# DarlingtonBJTArray.net
KiCad netlist of a schematic drawn in Altium Designer
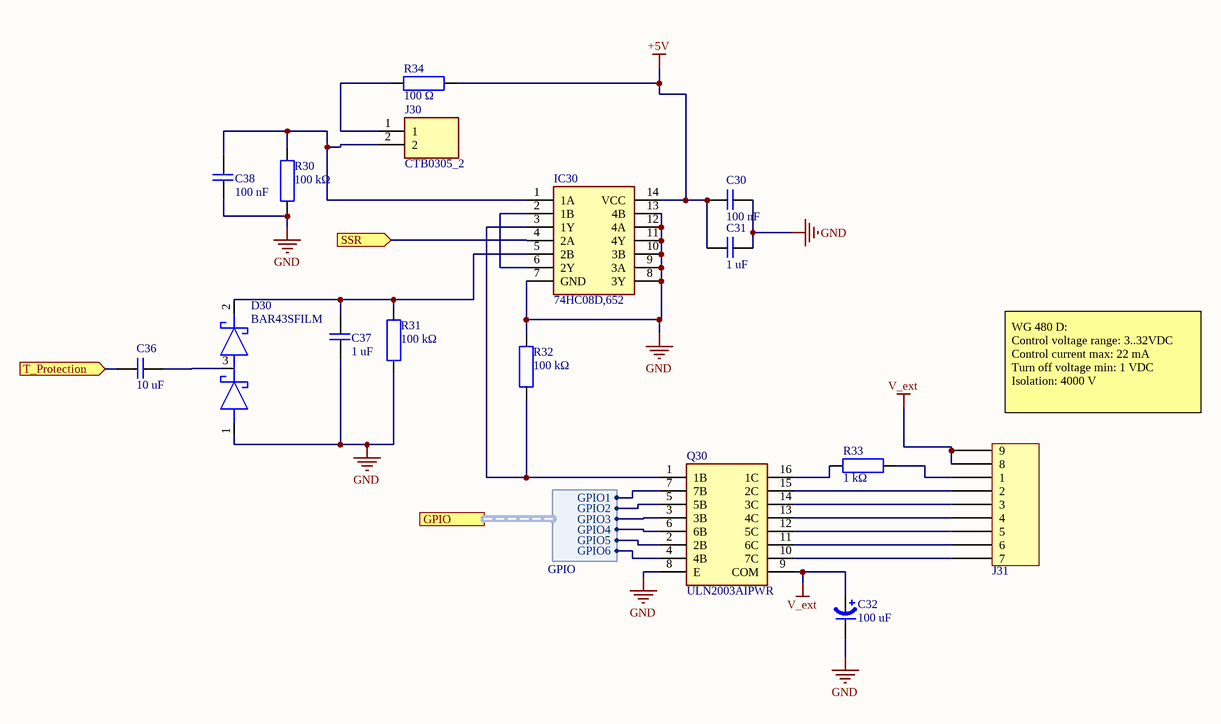
[diagram p0: DarlingtonBJTArray.SchDoc]

(export (version "E")
  (design (tool "Eeschema 10.0.6"))
  (components
    (comp (ref "C30")
      (value "100 nF")
      (footprint "1206 MLCC")
      (description "Generic MLCC")
      (libsource (lib "passives") (part "Capacitor"))
    )
    (comp (ref "C31")
      (value "1 uF")
      (footprint "1206 MLCC")
      (description "Generic MLCC")
      (libsource (lib "passives") (part "Capacitor"))
    )
    (comp (ref "C32")
      (value "100 uF")
      (footprint "RADIAL 8x11")
      (description "Electrolytic capacitor")
      (libsource (lib "passives") (part "Elco"))
    )
    (comp (ref "C36")
      (value "10 uF")
      (footprint "1210 MLCC")
      (description "Generic MLCC")
      (libsource (lib "passives") (part "Capacitor"))
    )
    (comp (ref "C37")
      (value "1 uF")
      (footprint "1206 MLCC")
      (description "Generic MLCC")
      (libsource (lib "passives") (part "Capacitor"))
    )
    (comp (ref "C38")
      (value "100 nF")
      (footprint "1206 MLCC")
      (description "Generic MLCC")
      (libsource (lib "passives") (part "Capacitor"))
    )
    (comp (ref "D30")
      (value "BAR43SFILM")
      (footprint "SamacSys:SOT105P242X150-3N")
      (description "Dual 0.1A small signl schottky")
      (fields (field (name "MOUSER PART NUMBER") "511-BAR43SFILM"))
      (libsource (lib "SamacSys") (part "BAR43SFILM"))
    )
    (comp (ref "IC30")
      (value "74HC08D,652")
      (footprint "SamacSys:SOIC127P600X175-14N")
      (description "Integrated Circuit")
      (fields (field (name "MOUSER PART NUMBER") "771-HC08D652"))
      (libsource (lib "*") (part "74HC08D,652"))
    )
    (comp (ref "J30")
      (value "CTB0305_2")
      (footprint "SamacSys:CTB03052")
      (description "Connector")
      (fields (field (name "MANUFACTURER_PART_NUMBER") "CTB0305/2"))
      (libsource (lib "*") (part "CTB0305_2"))
    )
    (comp (ref "J31")
      (value "9P terminal block")
      (footprint "9P terminal block 3.50mm")
      (description "3.50mm 9p terminal block")
      (libsource (lib "passives") (part "9P terminal block"))
    )
    (comp (ref "Q30")
      (value "ULN2003AIPWR")
      (footprint "SamacSys:SOP65P640X120-16N")
      (description "Transistor")
      (fields (field (name "MOUSER PART NUMBER") "595-ULN2003AIPWR"))
      (libsource (lib "*") (part "ULN2003AIPWR"))
    )
    (comp (ref "R30")
      (value "100 kΩ")
      (footprint "1206 RES")
      (description "Generic SMD resistor")
      (libsource (lib "") (part "Resitor_1"))
    )
    (comp (ref "R31")
      (value "100 kΩ")
      (footprint "1206 RES")
      (description "Generic SMD resistor")
      (libsource (lib "") (part "Resitor_1"))
    )
    (comp (ref "R32")
      (value "100 kΩ")
      (footprint "1206 RES")
      (description "Generic SMD resistor")
      (libsource (lib "") (part "Resitor_1"))
    )
    (comp (ref "R33")
      (value "1 kΩ")
      (footprint "1206 RES")
      (description "Generic SMD resistor")
      (libsource (lib "passives") (part "Resitor"))
    )
    (comp (ref "R34")
      (value "100 Ω")
      (footprint "1206 RES")
      (description "Generic SMD resistor")
      (libsource (lib "passives") (part "Resitor"))
    )
  )
  (nets
    (net (code "2") (name "+5V") (class "Default")
      (node (ref "C30") (pin "1") (pintype "passive"))
      (node (ref "C31") (pin "1") (pintype "passive"))
      (node (ref "IC30") (pin "14") (pinfunction "VCC_14") (pintype "passive"))
      (node (ref "R34") (pin "1") (pintype "passive"))
    )
    (net (code "3") (name "/GPIO1") (class "Default")
      (node (ref "Q30") (pin "7") (pinfunction "7B_7") (pintype "passive"))
    )
    (net (code "4") (name "/GPIO2") (class "Default")
      (node (ref "Q30") (pin "5") (pinfunction "5B_5") (pintype "passive"))
    )
    (net (code "5") (name "/GPIO3") (class "Default")
      (node (ref "Q30") (pin "3") (pinfunction "3B_3") (pintype "passive"))
    )
    (net (code "6") (name "/GPIO4") (class "Default")
      (node (ref "Q30") (pin "6") (pinfunction "6B_6") (pintype "passive"))
    )
    (net (code "7") (name "/GPIO5") (class "Default")
      (node (ref "Q30") (pin "2") (pinfunction "2B_2") (pintype "passive"))
    )
    (net (code "8") (name "/GPIO6") (class "Default")
      (node (ref "Q30") (pin "4") (pinfunction "4B_4") (pintype "passive"))
    )
    (net (code "9") (name "/SSR") (class "Default")
      (node (ref "IC30") (pin "4") (pinfunction "2A_4") (pintype "passive"))
    )
    (net (code "10") (name "/T_Protection") (class "Default")
      (node (ref "C36") (pin "1") (pintype "passive"))
    )
    (net (code "12") (name "GND") (class "Default")
      (node (ref "C30") (pin "2") (pintype "passive"))
      (node (ref "C31") (pin "2") (pintype "passive"))
      (node (ref "C32") (pin "2") (pintype "passive"))
      (node (ref "C37") (pin "1") (pintype "passive"))
      (node (ref "C38") (pin "1") (pintype "passive"))
      (node (ref "D30") (pin "1") (pinfunction "A_1") (pintype "passive"))
      (node (ref "IC30") (pin "10") (pinfunction "3B_10") (pintype "passive"))
      (node (ref "IC30") (pin "11") (pinfunction "4Y_11") (pintype "passive"))
      (node (ref "IC30") (pin "12") (pinfunction "4A_12") (pintype "passive"))
      (node (ref "IC30") (pin "13") (pinfunction "4B_13") (pintype "passive"))
      (node (ref "IC30") (pin "7") (pinfunction "GND_7") (pintype "passive"))
      (node (ref "IC30") (pin "8") (pinfunction "3Y_8") (pintype "passive"))
      (node (ref "IC30") (pin "9") (pinfunction "3A_9") (pintype "passive"))
      (node (ref "Q30") (pin "8") (pinfunction "E_8") (pintype "passive"))
      (node (ref "R30") (pin "2") (pintype "passive"))
      (node (ref "R31") (pin "2") (pintype "passive"))
      (node (ref "R32") (pin "1") (pintype "passive"))
    )
    (net (code "13") (name "Net-(C36-Pad2)") (class "Default")
      (node (ref "C36") (pin "2") (pintype "passive"))
      (node (ref "D30") (pin "3") (pinfunction "A_3") (pintype "passive"))
    )
    (net (code "14") (name "Net-(D30-K)") (class "Default")
      (node (ref "C37") (pin "2") (pintype "passive"))
      (node (ref "D30") (pin "2") (pinfunction "K_2") (pintype "passive"))
      (node (ref "IC30") (pin "5") (pinfunction "2B_5") (pintype "passive"))
      (node (ref "R31") (pin "1") (pintype "passive"))
    )
    (net (code "15") (name "Net-(IC30-1A)") (class "Default")
      (node (ref "C38") (pin "2") (pintype "passive"))
      (node (ref "IC30") (pin "1") (pinfunction "1A_1") (pintype "passive"))
      (node (ref "J30") (pin "2") (pinfunction "2_2") (pintype "passive"))
      (node (ref "R30") (pin "1") (pintype "passive"))
    )
    (net (code "16") (name "Net-(IC30-1B)") (class "Default")
      (node (ref "IC30") (pin "2") (pinfunction "1B_2") (pintype "passive"))
      (node (ref "IC30") (pin "6") (pinfunction "2Y_6") (pintype "passive"))
    )
    (net (code "17") (name "Net-(IC30-1Y)") (class "Default")
      (node (ref "IC30") (pin "3") (pinfunction "1Y_3") (pintype "passive"))
      (node (ref "Q30") (pin "1") (pinfunction "1B_1") (pintype "passive"))
      (node (ref "R32") (pin "2") (pintype "passive"))
    )
    (net (code "18") (name "Net-(J30-Pad1)") (class "Default")
      (node (ref "J30") (pin "1") (pinfunction "1_1") (pintype "passive"))
      (node (ref "R34") (pin "2") (pintype "passive"))
    )
    (net (code "19") (name "Net-(J31-Pad1)") (class "Default")
      (node (ref "J31") (pin "1") (pinfunction "1_1") (pintype "passive"))
      (node (ref "R33") (pin "1") (pintype "passive"))
    )
    (net (code "20") (name "Net-(Q30-1C)") (class "Default")
      (node (ref "Q30") (pin "16") (pinfunction "1C_16") (pintype "passive"))
      (node (ref "R33") (pin "2") (pintype "passive"))
    )
    (net (code "21") (name "Net-(Q30-2C)") (class "Default")
      (node (ref "J31") (pin "2") (pinfunction "2_2") (pintype "passive"))
      (node (ref "Q30") (pin "15") (pinfunction "2C_15") (pintype "passive"))
    )
    (net (code "22") (name "Net-(Q30-3C)") (class "Default")
      (node (ref "J31") (pin "3") (pinfunction "3_3") (pintype "passive"))
      (node (ref "Q30") (pin "14") (pinfunction "3C_14") (pintype "passive"))
    )
    (net (code "23") (name "Net-(Q30-4C)") (class "Default")
      (node (ref "J31") (pin "4") (pinfunction "4_4") (pintype "passive"))
      (node (ref "Q30") (pin "13") (pinfunction "4C_13") (pintype "passive"))
    )
    (net (code "24") (name "Net-(Q30-5C)") (class "Default")
      (node (ref "J31") (pin "5") (pinfunction "5_5") (pintype "passive"))
      (node (ref "Q30") (pin "12") (pinfunction "5C_12") (pintype "passive"))
    )
    (net (code "25") (name "Net-(Q30-6C)") (class "Default")
      (node (ref "J31") (pin "6") (pinfunction "6_6") (pintype "passive"))
      (node (ref "Q30") (pin "11") (pinfunction "6C_11") (pintype "passive"))
    )
    (net (code "26") (name "Net-(Q30-7C)") (class "Default")
      (node (ref "J31") (pin "7") (pinfunction "7_7") (pintype "passive"))
      (node (ref "Q30") (pin "10") (pinfunction "7C_10") (pintype "passive"))
    )
    (net (code "27") (name "V_ext") (class "Default")
      (node (ref "C32") (pin "1") (pintype "passive"))
      (node (ref "J31") (pin "8") (pinfunction "8_8") (pintype "passive"))
      (node (ref "J31") (pin "9") (pinfunction "9_9") (pintype "passive"))
      (node (ref "Q30") (pin "9") (pinfunction "COM_9") (pintype "passive"))
    )
  )
)
